# Pasa_bandas.net
KiCad netlist of a schematic drawn in Altium Designer
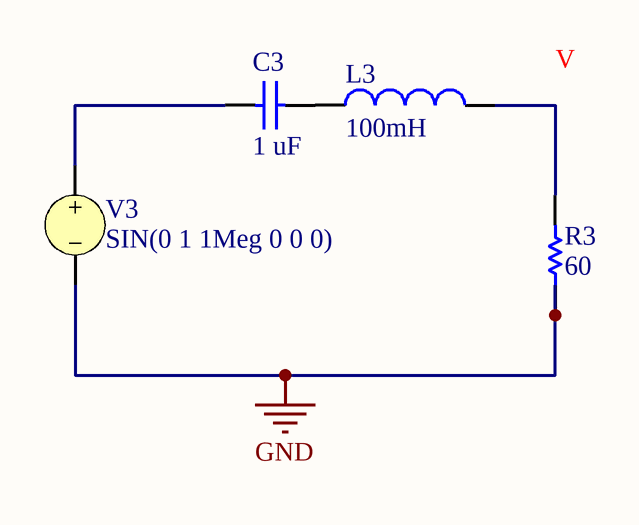
[diagram p0: Pasa_bandas.SchDoc]

(export (version "E")
  (design (tool "Eeschema 10.0.6"))
  (components
    (comp (ref "C3")
      (value "1 uF")
      (description "Capacitor")
      (libsource (lib "Simulation Generic Components") (part "Capacitor"))
    )
    (comp (ref "L3")
      (value "100mH")
      (description "Inductor")
      (libsource (lib "Simulation Generic Components") (part "Inductor"))
    )
    (comp (ref "R3")
      (value "60")
      (description "Resistor")
      (libsource (lib "Simulation Generic Components") (part "Resistor"))
    )
    (comp (ref "V3")
      (value "SIN(0 1 1Meg 0 0 0)")
      (description "Voltage Source")
      (fields (field (name "PUBLISHER") "Altium Limited"))
      (libsource (lib "Simulation Generic Components") (part "VSRC"))
    )
  )
  (nets
    (net (code "1") (name "GND") (class "Default")
      (node (ref "R3") (pin "1") (pinfunction "1_1") (pintype "passive"))
      (node (ref "V3") (pin "2") (pinfunction "2_2") (pintype "passive"))
    )
    (net (code "2") (name "Net-(C3-Pad1)") (class "Default")
      (node (ref "C3") (pin "1") (pinfunction "1_1") (pintype "passive"))
      (node (ref "V3") (pin "1") (pinfunction "1_1") (pintype "passive"))
    )
    (net (code "3") (name "Net-(C3-Pad2)") (class "Default")
      (node (ref "C3") (pin "2") (pinfunction "2_2") (pintype "passive"))
      (node (ref "L3") (pin "1") (pinfunction "1_1") (pintype "passive"))
    )
    (net (code "4") (name "Net-(L3-Pad2)") (class "Default")
      (node (ref "L3") (pin "2") (pinfunction "2_2") (pintype "passive"))
      (node (ref "R3") (pin "2") (pinfunction "2_2") (pintype "passive"))
    )
  )
)
